# motorcontroller_doppeleinheit.net
KiCad netlist of a schematic drawn in EAGLE
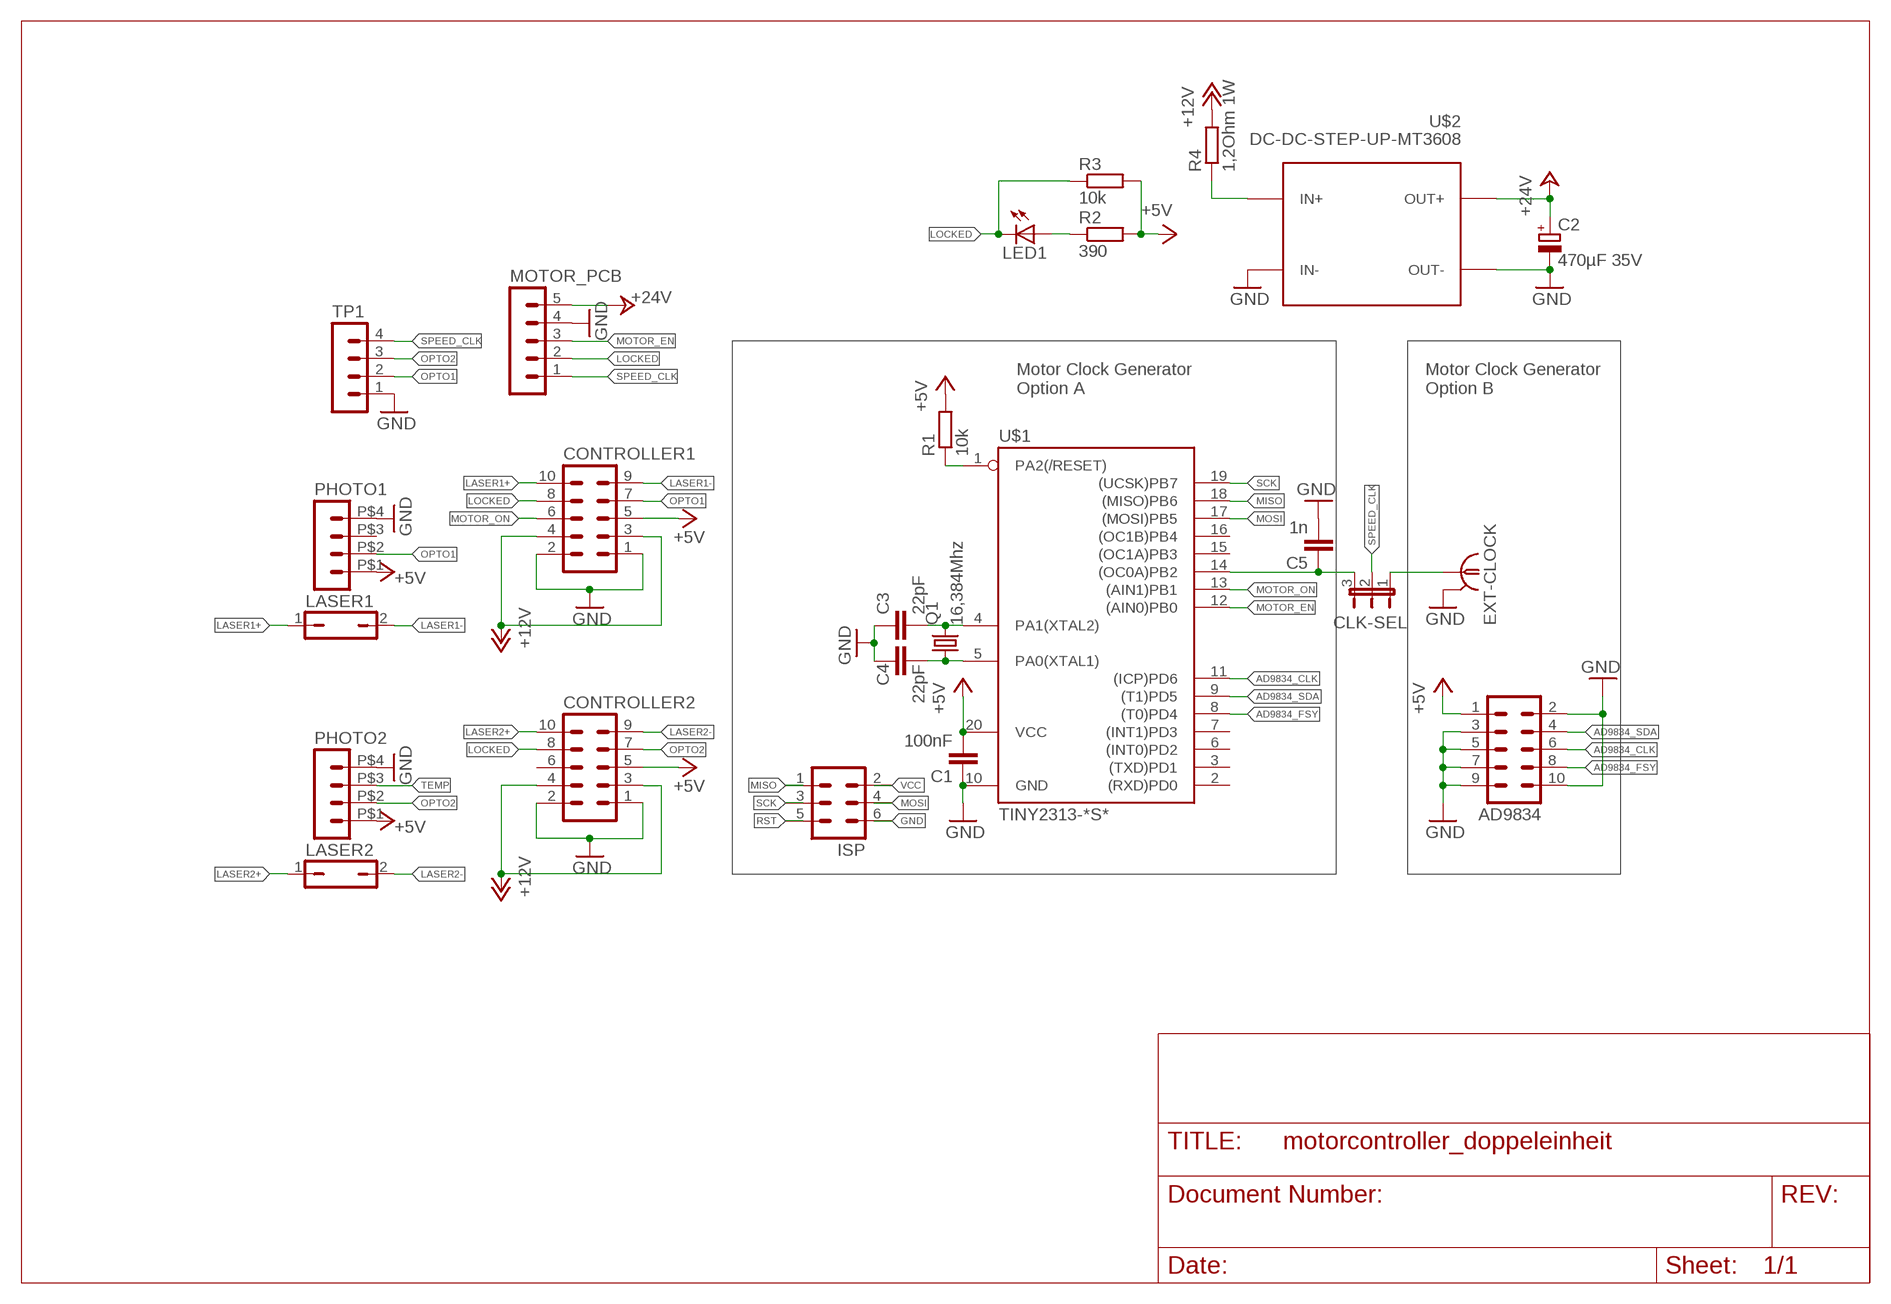
[diagram p0: schematic, sheet 1]

(export (version "E")
  (design (tool "Eeschema 10.0.6"))
  (components
    (comp (ref "AD9834")
      (value "ML10")
      (footprint "eagle-import:ML10")
      (libsource (lib "eagle-import") (part "ML10"))
    )
    (comp (ref "C1")
      (value "100nF")
      (footprint "eagle-import:C1206")
      (libsource (lib "eagle-import") (part "C-EUC1206"))
    )
    (comp (ref "C2")
      (value "470µF 35V")
      (footprint "eagle-import:E5-6")
      (libsource (lib "eagle-import") (part "CPOL-EUE5-6"))
    )
    (comp (ref "C3")
      (value "22pF")
      (footprint "eagle-import:C1206")
      (libsource (lib "eagle-import") (part "C-EUC1206"))
    )
    (comp (ref "C4")
      (value "22pF")
      (footprint "eagle-import:C1206")
      (libsource (lib "eagle-import") (part "C-EUC1206"))
    )
    (comp (ref "C5")
      (value "1n")
      (footprint "eagle-import:C1206")
      (libsource (lib "eagle-import") (part "C-EUC1206"))
    )
    (comp (ref "CLK-SEL")
      (value "JP2E")
      (footprint "eagle-import:JP2")
      (libsource (lib "eagle-import") (part "JP2E"))
    )
    (comp (ref "CONTROLLER1")
      (value "ML10")
      (footprint "eagle-import:ML10")
      (libsource (lib "eagle-import") (part "ML10"))
    )
    (comp (ref "CONTROLLER2")
      (value "ML10")
      (footprint "eagle-import:ML10")
      (libsource (lib "eagle-import") (part "ML10"))
    )
    (comp (ref "EXT-CLOCK")
      (value "LTI-SASF54GT")
      (footprint "eagle-import:LTI-SASF54GT")
      (libsource (lib "eagle-import") (part "LTI-SASF54GT"))
    )
    (comp (ref "ISP")
      (value "ML6L")
      (footprint "eagle-import:ML6L")
      (libsource (lib "eagle-import") (part "ML6L"))
    )
    (comp (ref "LASER1")
      (value "JP1Q")
      (footprint "eagle-import:JP1")
      (libsource (lib "eagle-import") (part "JP1Q"))
    )
    (comp (ref "LASER2")
      (value "JP1Q")
      (footprint "eagle-import:JP1")
      (libsource (lib "eagle-import") (part "JP1Q"))
    )
    (comp (ref "LED1")
      (value "LED3MM")
      (footprint "eagle-import:LED3MM")
      (libsource (lib "eagle-import") (part "LED3MM"))
    )
    (comp (ref "MOTOR_PCB")
      (value "MA05-1")
      (footprint "eagle-import:MA05-1")
      (libsource (lib "eagle-import") (part "MA05-1"))
    )
    (comp (ref "PHOTO1")
      (value "FLAT_P4")
      (footprint "eagle-import:FLAT_4P")
      (libsource (lib "eagle-import") (part "FLAT_P4"))
    )
    (comp (ref "PHOTO2")
      (value "FLAT_P4")
      (footprint "eagle-import:FLAT_4P")
      (libsource (lib "eagle-import") (part "FLAT_P4"))
    )
    (comp (ref "Q1")
      (value "16,384Mhz")
      (footprint "eagle-import:HC49UP")
      (libsource (lib "eagle-import") (part "CRYSTALHC49UP"))
    )
    (comp (ref "R1")
      (value "10k")
      (footprint "eagle-import:R1206")
      (libsource (lib "eagle-import") (part "R-EU_R1206"))
    )
    (comp (ref "R2")
      (value "390")
      (footprint "eagle-import:R1206")
      (libsource (lib "eagle-import") (part "R-EU_R1206"))
    )
    (comp (ref "R3")
      (value "10k")
      (footprint "eagle-import:R1206")
      (libsource (lib "eagle-import") (part "R-EU_R1206"))
    )
    (comp (ref "R4")
      (value "1,2Ohm 1W")
      (footprint "eagle-import:0411_15")
      (libsource (lib "eagle-import") (part "R-EU_0411/15"))
    )
    (comp (ref "TP1")
      (value "MA04-1")
      (footprint "eagle-import:MA04-1")
      (libsource (lib "eagle-import") (part "MA04-1"))
    )
    (comp (ref "U$1")
      (value "TINY2313-*S*")
      (footprint "eagle-import:SO20L$")
      (libsource (lib "eagle-import") (part "TINY2313-S"))
    )
    (comp (ref "U$2")
      (value "DC-DC-STEP-UP-MT3608")
      (footprint "eagle-import:DC-DC-STEP-UP-MT3608")
      (libsource (lib "eagle-import") (part "DC-DC-STEP-UP-MT3608"))
    )
  )
  (nets
    (net (code "1") (name "+5V") (class "Default")
      (node (ref "AD9834") (pin "1") (pinfunction "1_1") (pintype "passive"))
      (node (ref "C1") (pin "2") (pinfunction "2_2") (pintype "passive"))
      (node (ref "CONTROLLER1") (pin "5") (pinfunction "5_5") (pintype "passive"))
      (node (ref "CONTROLLER2") (pin "5") (pinfunction "5_5") (pintype "passive"))
      (node (ref "PHOTO1") (pin "P$1") (pinfunction "1_P$1") (pintype "passive"))
      (node (ref "PHOTO2") (pin "P$1") (pinfunction "1_P$1") (pintype "passive"))
      (node (ref "R1") (pin "2") (pinfunction "2_2") (pintype "passive"))
      (node (ref "R2") (pin "2") (pinfunction "2_2") (pintype "passive"))
      (node (ref "R3") (pin "2") (pinfunction "2_2") (pintype "passive"))
      (node (ref "U$1") (pin "20") (pinfunction "VCC_20") (pintype "power_in"))
    )
    (net (code "2") (name "+12V") (class "Default")
      (node (ref "CONTROLLER1") (pin "3") (pinfunction "3_3") (pintype "passive"))
      (node (ref "CONTROLLER1") (pin "4") (pinfunction "4_4") (pintype "passive"))
      (node (ref "CONTROLLER2") (pin "3") (pinfunction "3_3") (pintype "passive"))
      (node (ref "CONTROLLER2") (pin "4") (pinfunction "4_4") (pintype "passive"))
      (node (ref "R4") (pin "2") (pinfunction "2_2") (pintype "passive"))
    )
    (net (code "3") (name "+24V") (class "Default")
      (node (ref "C2") (pin "+") (pinfunction "+_+") (pintype "passive"))
      (node (ref "MOTOR_PCB") (pin "5") (pinfunction "5_5") (pintype "passive"))
      (node (ref "U$2") (pin "OUT+") (pinfunction "OUT+_OUT+") (pintype "bidirectional"))
    )
    (net (code "4") (name "AD9834_CLK") (class "Default")
      (node (ref "AD9834") (pin "6") (pinfunction "6_6") (pintype "passive"))
      (node (ref "U$1") (pin "11") (pinfunction "(ICP)PD6_11") (pintype "bidirectional"))
    )
    (net (code "5") (name "AD9834_FSY") (class "Default")
      (node (ref "AD9834") (pin "8") (pinfunction "8_8") (pintype "passive"))
      (node (ref "U$1") (pin "8") (pinfunction "(T0)PD4_8") (pintype "bidirectional"))
    )
    (net (code "6") (name "AD9834_SDA") (class "Default")
      (node (ref "AD9834") (pin "4") (pinfunction "4_4") (pintype "passive"))
      (node (ref "U$1") (pin "9") (pinfunction "(T1)PD5_9") (pintype "bidirectional"))
    )
    (net (code "7") (name "GND") (class "Default")
      (node (ref "AD9834") (pin "10") (pinfunction "10_10") (pintype "passive"))
      (node (ref "AD9834") (pin "2") (pinfunction "2_2") (pintype "passive"))
      (node (ref "AD9834") (pin "3") (pinfunction "3_3") (pintype "passive"))
      (node (ref "AD9834") (pin "5") (pinfunction "5_5") (pintype "passive"))
      (node (ref "AD9834") (pin "7") (pinfunction "7_7") (pintype "passive"))
      (node (ref "AD9834") (pin "9") (pinfunction "9_9") (pintype "passive"))
      (node (ref "C1") (pin "1") (pinfunction "1_1") (pintype "passive"))
      (node (ref "C2") (pin "-") (pinfunction "-_-") (pintype "passive"))
      (node (ref "C3") (pin "1") (pinfunction "1_1") (pintype "passive"))
      (node (ref "C4") (pin "1") (pinfunction "1_1") (pintype "passive"))
      (node (ref "C5") (pin "2") (pinfunction "2_2") (pintype "passive"))
      (node (ref "CONTROLLER1") (pin "1") (pinfunction "1_1") (pintype "passive"))
      (node (ref "CONTROLLER1") (pin "2") (pinfunction "2_2") (pintype "passive"))
      (node (ref "CONTROLLER2") (pin "1") (pinfunction "1_1") (pintype "passive"))
      (node (ref "CONTROLLER2") (pin "2") (pinfunction "2_2") (pintype "passive"))
      (node (ref "EXT-CLOCK") (pin "2") (pinfunction "2_2") (pintype "passive"))
      (node (ref "EXT-CLOCK") (pin "3") (pinfunction "2_3") (pintype "passive"))
      (node (ref "EXT-CLOCK") (pin "4") (pinfunction "2_4") (pintype "passive"))
      (node (ref "EXT-CLOCK") (pin "5") (pinfunction "2_5") (pintype "passive"))
      (node (ref "ISP") (pin "6") (pinfunction "6_6") (pintype "passive"))
      (node (ref "MOTOR_PCB") (pin "4") (pinfunction "4_4") (pintype "passive"))
      (node (ref "PHOTO1") (pin "P$4") (pinfunction "4_P$4") (pintype "passive"))
      (node (ref "PHOTO2") (pin "P$4") (pinfunction "4_P$4") (pintype "passive"))
      (node (ref "TP1") (pin "1") (pinfunction "1_1") (pintype "passive"))
      (node (ref "U$1") (pin "10") (pinfunction "GND_10") (pintype "power_in"))
      (node (ref "U$2") (pin "IN-") (pinfunction "IN-_IN-") (pintype "bidirectional"))
      (node (ref "U$2") (pin "OUT-") (pinfunction "OUT-_OUT-") (pintype "bidirectional"))
    )
    (net (code "8") (name "LASER1+") (class "Default")
      (node (ref "CONTROLLER1") (pin "10") (pinfunction "10_10") (pintype "passive"))
      (node (ref "LASER1") (pin "1") (pinfunction "1_1") (pintype "passive"))
    )
    (net (code "9") (name "LASER1-") (class "Default")
      (node (ref "CONTROLLER1") (pin "9") (pinfunction "9_9") (pintype "passive"))
      (node (ref "LASER1") (pin "2") (pinfunction "2_2") (pintype "passive"))
    )
    (net (code "10") (name "LASER2+") (class "Default")
      (node (ref "CONTROLLER2") (pin "10") (pinfunction "10_10") (pintype "passive"))
      (node (ref "LASER2") (pin "1") (pinfunction "1_1") (pintype "passive"))
    )
    (net (code "11") (name "LASER2-") (class "Default")
      (node (ref "CONTROLLER2") (pin "9") (pinfunction "9_9") (pintype "passive"))
      (node (ref "LASER2") (pin "2") (pinfunction "2_2") (pintype "passive"))
    )
    (net (code "12") (name "LOCKED") (class "Default")
      (node (ref "CONTROLLER1") (pin "8") (pinfunction "8_8") (pintype "passive"))
      (node (ref "CONTROLLER2") (pin "8") (pinfunction "8_8") (pintype "passive"))
      (node (ref "LED1") (pin "K") (pinfunction "C_K") (pintype "passive"))
      (node (ref "MOTOR_PCB") (pin "2") (pinfunction "2_2") (pintype "passive"))
      (node (ref "R3") (pin "1") (pinfunction "1_1") (pintype "passive"))
    )
    (net (code "13") (name "MISO") (class "Default")
      (node (ref "ISP") (pin "1") (pinfunction "1_1") (pintype "passive"))
      (node (ref "U$1") (pin "18") (pinfunction "(MISO)PB6_18") (pintype "bidirectional"))
    )
    (net (code "14") (name "MOSI") (class "Default")
      (node (ref "ISP") (pin "4") (pinfunction "4_4") (pintype "passive"))
      (node (ref "U$1") (pin "17") (pinfunction "(MOSI)PB5_17") (pintype "bidirectional"))
    )
    (net (code "15") (name "MOTOR_EN") (class "Default")
      (node (ref "MOTOR_PCB") (pin "3") (pinfunction "3_3") (pintype "passive"))
      (node (ref "U$1") (pin "12") (pinfunction "(AIN0)PB0_12") (pintype "bidirectional"))
    )
    (net (code "16") (name "MOTOR_ON") (class "Default")
      (node (ref "CONTROLLER1") (pin "6") (pinfunction "6_6") (pintype "passive"))
      (node (ref "U$1") (pin "13") (pinfunction "(AIN1)PB1_13") (pintype "bidirectional"))
    )
    (net (code "17") (name "Net-(CLK-SEL-Pad1)") (class "Default")
      (node (ref "CLK-SEL") (pin "1") (pinfunction "1_1") (pintype "passive"))
      (node (ref "EXT-CLOCK") (pin "1") (pinfunction "1_1") (pintype "passive"))
    )
    (net (code "18") (name "Net-(LED1-PadA)") (class "Default")
      (node (ref "LED1") (pin "A") (pinfunction "A_A") (pintype "passive"))
      (node (ref "R2") (pin "1") (pinfunction "1_1") (pintype "passive"))
    )
    (net (code "19") (name "Net-(R4-Pad1)") (class "Default")
      (node (ref "R4") (pin "1") (pinfunction "1_1") (pintype "passive"))
      (node (ref "U$2") (pin "IN+") (pinfunction "IN+_IN+") (pintype "bidirectional"))
    )
    (net (code "20") (name "Net-(U$1-(OC0A)PB2)") (class "Default")
      (node (ref "C5") (pin "1") (pinfunction "1_1") (pintype "passive"))
      (node (ref "CLK-SEL") (pin "3") (pinfunction "3_3") (pintype "passive"))
      (node (ref "U$1") (pin "14") (pinfunction "(OC0A)PB2_14") (pintype "bidirectional"))
    )
    (net (code "21") (name "Net-(U$1-PA0(XTAL1))") (class "Default")
      (node (ref "C4") (pin "2") (pinfunction "2_2") (pintype "passive"))
      (node (ref "Q1") (pin "1") (pinfunction "1_1") (pintype "passive"))
      (node (ref "U$1") (pin "5") (pinfunction "PA0(XTAL1)_5") (pintype "bidirectional"))
    )
    (net (code "22") (name "Net-(U$1-PA1(XTAL2))") (class "Default")
      (node (ref "C3") (pin "2") (pinfunction "2_2") (pintype "passive"))
      (node (ref "Q1") (pin "2") (pinfunction "2_2") (pintype "passive"))
      (node (ref "U$1") (pin "4") (pinfunction "PA1(XTAL2)_4") (pintype "bidirectional"))
    )
    (net (code "23") (name "OPTO1") (class "Default")
      (node (ref "CONTROLLER1") (pin "7") (pinfunction "7_7") (pintype "passive"))
      (node (ref "PHOTO1") (pin "P$2") (pinfunction "2_P$2") (pintype "passive"))
      (node (ref "TP1") (pin "2") (pinfunction "2_2") (pintype "passive"))
    )
    (net (code "24") (name "OPTO2") (class "Default")
      (node (ref "CONTROLLER2") (pin "7") (pinfunction "7_7") (pintype "passive"))
      (node (ref "PHOTO2") (pin "P$2") (pinfunction "2_P$2") (pintype "passive"))
      (node (ref "TP1") (pin "3") (pinfunction "3_3") (pintype "passive"))
    )
    (net (code "25") (name "RST") (class "Default")
      (node (ref "ISP") (pin "5") (pinfunction "5_5") (pintype "passive"))
      (node (ref "R1") (pin "1") (pinfunction "1_1") (pintype "passive"))
      (node (ref "U$1") (pin "1") (pinfunction "PA2(/RESET)_1") (pintype "input"))
    )
    (net (code "26") (name "SCK") (class "Default")
      (node (ref "ISP") (pin "3") (pinfunction "3_3") (pintype "passive"))
      (node (ref "U$1") (pin "19") (pinfunction "(UCSK)PB7_19") (pintype "bidirectional"))
    )
    (net (code "27") (name "SPEED_CLK") (class "Default")
      (node (ref "CLK-SEL") (pin "2") (pinfunction "2_2") (pintype "passive"))
      (node (ref "MOTOR_PCB") (pin "1") (pinfunction "1_1") (pintype "passive"))
      (node (ref "TP1") (pin "4") (pinfunction "4_4") (pintype "passive"))
    )
    (net (code "28") (name "TEMP") (class "Default")
      (node (ref "PHOTO2") (pin "P$3") (pinfunction "3_P$3") (pintype "passive"))
    )
    (net (code "29") (name "VCC") (class "Default")
      (node (ref "ISP") (pin "2") (pinfunction "2_2") (pintype "passive"))
    )
    (net (code "30") (name "unconnected-(CONTROLLER2-Pad6)") (class "Default")
      (node (ref "CONTROLLER2") (pin "6") (pinfunction "6_6") (pintype "passive"))
    )
    (net (code "31") (name "unconnected-(PHOTO1-3-PadP$3)") (class "Default")
      (node (ref "PHOTO1") (pin "P$3") (pinfunction "3_P$3") (pintype "passive"))
    )
    (net (code "32") (name "unconnected-(U$1-(INT0)PD2-Pad6)") (class "Default")
      (node (ref "U$1") (pin "6") (pinfunction "(INT0)PD2_6") (pintype "bidirectional"))
    )
    (net (code "33") (name "unconnected-(U$1-(INT1)PD3-Pad7)") (class "Default")
      (node (ref "U$1") (pin "7") (pinfunction "(INT1)PD3_7") (pintype "bidirectional"))
    )
    (net (code "34") (name "unconnected-(U$1-(OC1A)PB3-Pad15)") (class "Default")
      (node (ref "U$1") (pin "15") (pinfunction "(OC1A)PB3_15") (pintype "bidirectional"))
    )
    (net (code "35") (name "unconnected-(U$1-(OC1B)PB4-Pad16)") (class "Default")
      (node (ref "U$1") (pin "16") (pinfunction "(OC1B)PB4_16") (pintype "bidirectional"))
    )
    (net (code "36") (name "unconnected-(U$1-(RXD)PD0-Pad2)") (class "Default")
      (node (ref "U$1") (pin "2") (pinfunction "(RXD)PD0_2") (pintype "bidirectional"))
    )
    (net (code "37") (name "unconnected-(U$1-(TXD)PD1-Pad3)") (class "Default")
      (node (ref "U$1") (pin "3") (pinfunction "(TXD)PD1_3") (pintype "bidirectional"))
    )
  )
)
